# CAN.net
KiCad netlist of a schematic drawn in Altium Designer
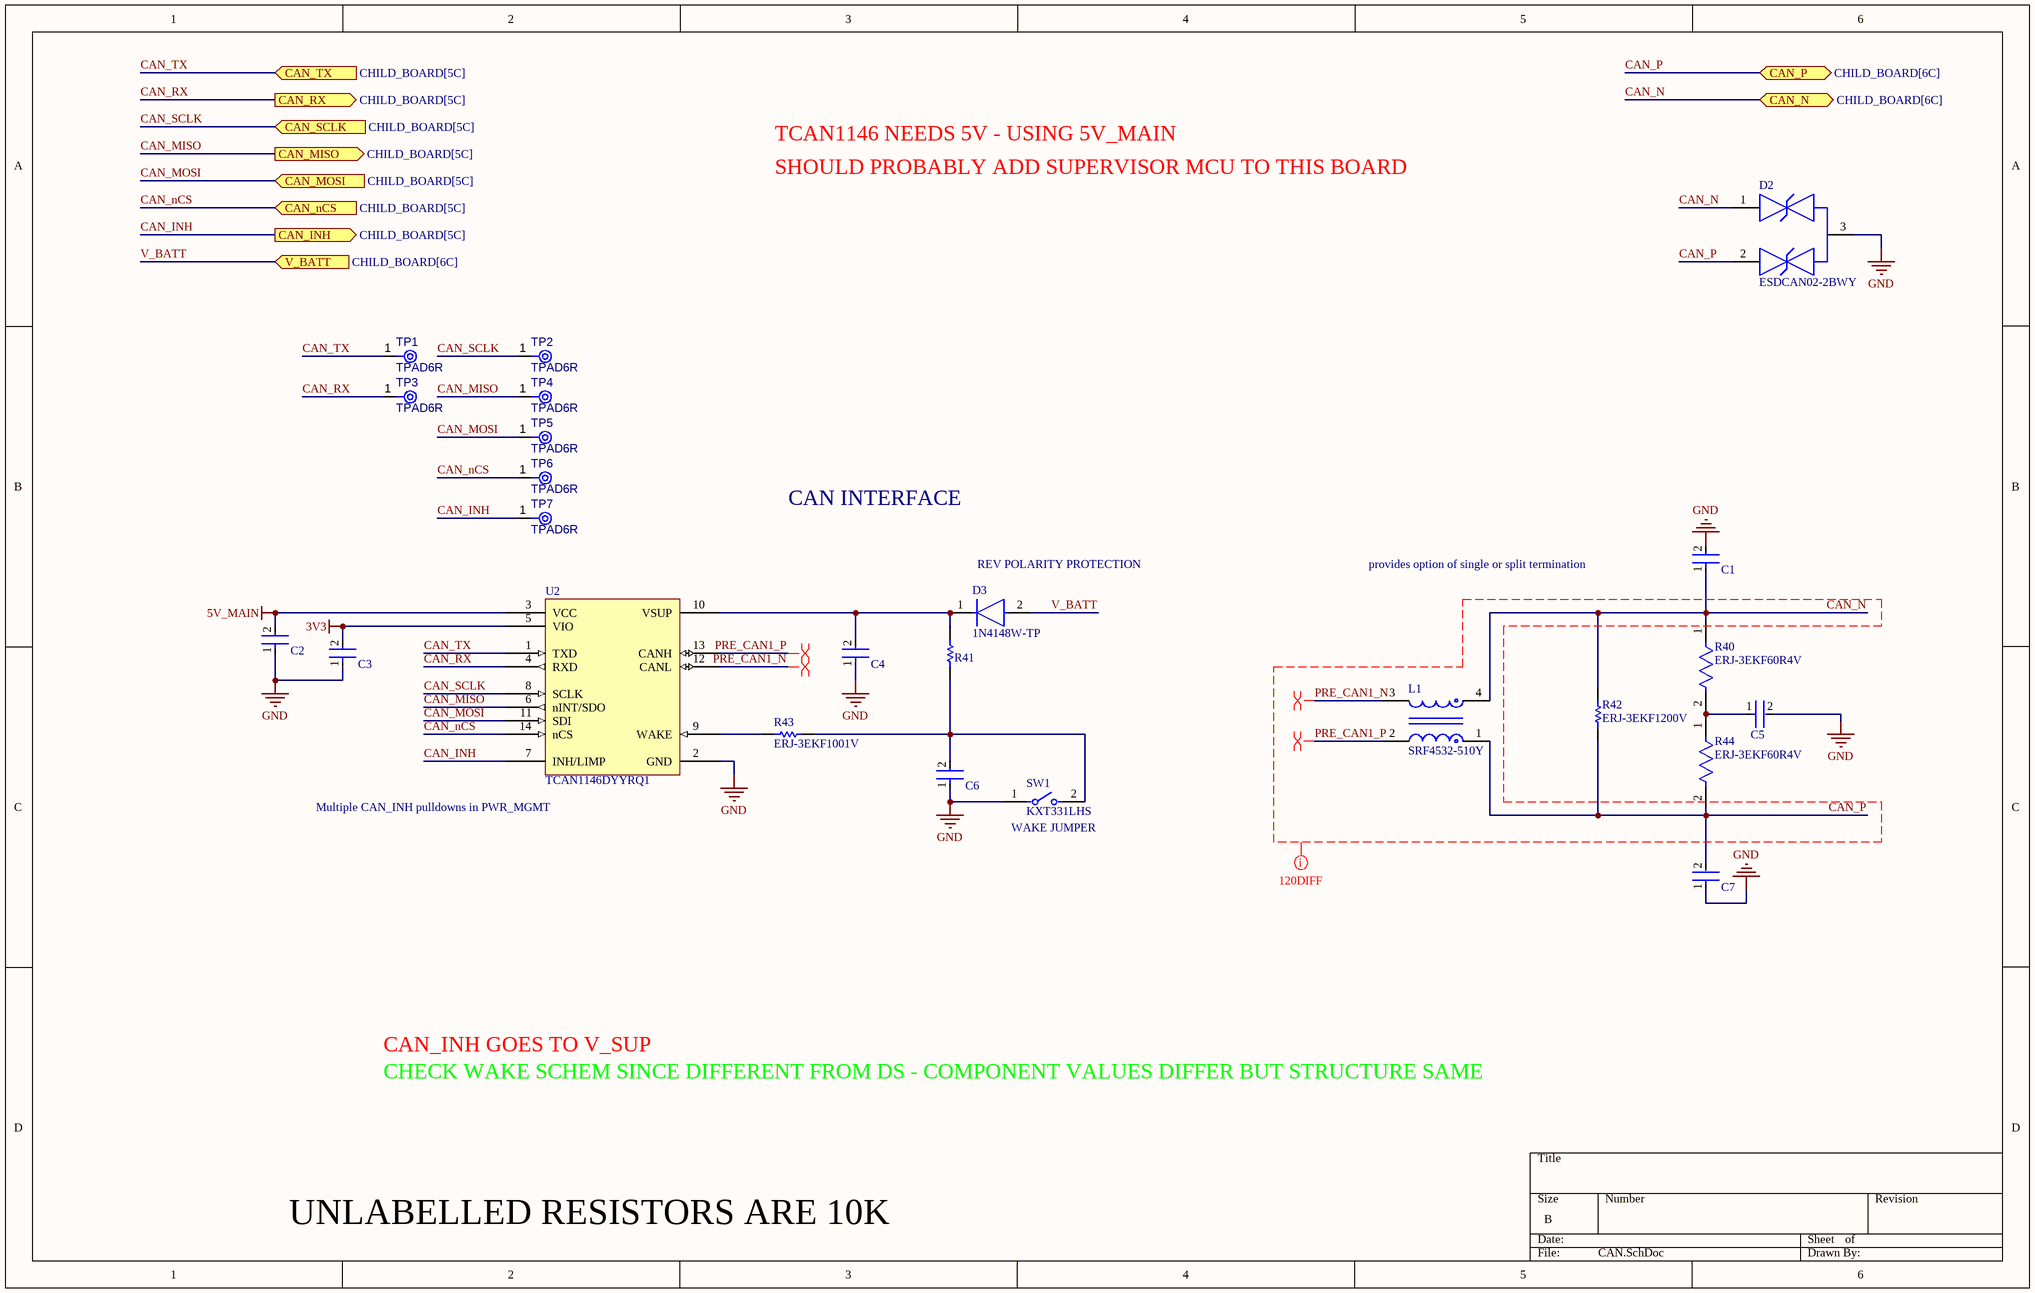
[diagram p0: CAN.SchDoc]

(export (version "E")
  (design (tool "Eeschema 10.0.6"))
  (components
    (comp (ref "C1")
      (value "C0402C104K8PACTU")
      (footprint "FP-C0402-BB-MFG")
      (description "CAP CER 0.1UF 10V X5R 0402")
      (fields (field (name "MANUFACTURER") "Kemet") (field (name "TOLERANCE") "0.1"))
      (libsource (lib "Altium Content Vault") (part "b4654b650e69147ec39a6b967a45e02"))
    )
    (comp (ref "C2")
      (value "C0402C104K8PACTU")
      (footprint "FP-C0402-BB-MFG")
      (description "CAP CER 0.1UF 10V X5R 0402")
      (fields (field (name "MANUFACTURER") "Kemet") (field (name "TOLERANCE") "0.1"))
      (libsource (lib "Altium Content Vault") (part "b4654b650e69147ec39a6b967a45e02"))
    )
    (comp (ref "C3")
      (value "C0402C104K8PACTU")
      (footprint "FP-C0402-BB-MFG")
      (description "CAP CER 0.1UF 10V X5R 0402")
      (fields (field (name "MANUFACTURER") "Kemet") (field (name "TOLERANCE") "0.1"))
      (libsource (lib "Altium Content Vault") (part "b4654b650e69147ec39a6b967a45e02"))
    )
    (comp (ref "C4")
      (value "C0402C104K8PACTU")
      (footprint "FP-C0402-BB-MFG")
      (description "CAP CER 0.1UF 10V X5R 0402")
      (fields (field (name "MANUFACTURER") "Kemet") (field (name "TOLERANCE") "0.1"))
      (libsource (lib "Altium Content Vault") (part "b4654b650e69147ec39a6b967a45e02"))
    )
    (comp (ref "C5")
      (value "C0402C104K8PACTU")
      (footprint "FP-C0402-BB-MFG")
      (description "CAP CER 0.1UF 10V X5R 0402")
      (fields (field (name "MANUFACTURER") "Kemet") (field (name "TOLERANCE") "0.1"))
      (libsource (lib "Altium Content Vault") (part "b4654b650e69147ec39a6b967a45e02"))
    )
    (comp (ref "C6")
      (value "C0402C104K8PACTU")
      (footprint "FP-C0402-BB-MFG")
      (description "CAP CER 0.1UF 10V X5R 0402")
      (fields (field (name "MANUFACTURER") "Kemet") (field (name "TOLERANCE") "0.1"))
      (libsource (lib "Altium Content Vault") (part "b4654b650e69147ec39a6b967a45e02"))
    )
    (comp (ref "C7")
      (value "C0402C104K8PACTU")
      (footprint "FP-C0402-BB-MFG")
      (description "CAP CER 0.1UF 10V X5R 0402")
      (fields (field (name "MANUFACTURER") "Kemet") (field (name "TOLERANCE") "0.1"))
      (libsource (lib "Altium Content Vault") (part "b4654b650e69147ec39a6b967a45e02"))
    )
    (comp (ref "D2")
      (value "ESDCAN02-2BWY")
      (footprint "FP-SOT323-3L-MFG")
      (description "TVS DIODE 26.5V 44V SOT323-3")
      (fields
        (field (name "MANUFACTURER") "STMicroelectronics")
        (field (name "OCTOPART") "https://octopart.com/esdcan02-2bwy-stmicroelectronics-58631133")
      )
      (libsource (lib "Altium Content Vault") (part "0b9019fb5e52ed66df21ec1535be59d"))
    )
    (comp (ref "D3")
      (value "1N4148W-TP")
      (footprint "FP-SOD-123-IPC_A")
      (description "DIODE GEN PURP 100V 150MA SOD123")
      (libsource (lib "Altium Content Vault") (part "d7152d700b627762746794eb795d46e"))
    )
    (comp (ref "L1")
      (value "SRF4532-510Y")
      (footprint "FP-SRF4532-MFG")
      (description "CMC 51UH 200MA 2LN 2KOHM SMD")
      (fields (field (name "TOLERANCE") "50%"))
      (libsource (lib "Altium Content Vault") (part "aca3f6a10b859f211cca95010157f3b"))
    )
    (comp (ref "R40")
      (value "ERJ-3EKF60R4V")
      (footprint "FP-ERJ3EK-IPC_C")
      (description "RES SMD 60.4 OHM 1% 1/10W 0603")
      (fields (field (name "TOLERANCE") "1%"))
      (libsource (lib "Altium Content Vault") (part "1029c3af85768c4190bb7ad29bc67b5"))
    )
    (comp (ref "R41")
      (value "ERJ3EKF1002V")
      (footprint "RESC1609X55X30LL15T15")
      (description "Chip Resistor, 10 KOhm, +/- 1%, 0.1 W, -55 to 155 degC, 0603 (1608 Metric), RoHS, Tape and Reel")
      (fields (field (name "TOLERANCE") "1%") (field (name "MANUFACTURER") "Panasonic"))
      (libsource (lib "Altium Content Vault") (part "RES-2"))
    )
    (comp (ref "R42")
      (value "ERJ-3EKF1200V")
      (footprint "RESC1609X55X30ML15T15")
      (description "Chip Resistor, 120 Ohm, +/- 1%, 0.1 W, -55 to 155 degC, 0603 (1608 Metric), RoHS, Tape and Reel")
      (fields (field (name "TOLERANCE") "1%") (field (name "MANUFACTURER") "Panasonic"))
      (libsource (lib "Altium Content Vault") (part "RES-2"))
    )
    (comp (ref "R43")
      (value "ERJ-3EKF1001V")
      (footprint "RESC1608X55X30LL15T15")
      (fields (field (name "MANUFACTURER") "Panasonic"))
      (libsource (lib "Altium Content Vault") (part "RES"))
    )
    (comp (ref "R44")
      (value "ERJ-3EKF60R4V")
      (footprint "FP-ERJ3EK-IPC_C")
      (description "RES SMD 60.4 OHM 1% 1/10W 0603")
      (fields (field (name "TOLERANCE") "1%"))
      (libsource (lib "Altium Content Vault") (part "1029c3af85768c4190bb7ad29bc67b5"))
    )
    (comp (ref "SW1")
      (value "KXT331LHS")
      (footprint "FP-KXT331LHS-MFG")
      (description "SWITCH TACTILE SPST-NO 0.02A 15V")
      (libsource (lib "Altium Content Vault") (part "bb27bde45df87f1f469753f287ef5ae"))
    )
    (comp (ref "TP1")
      (value "TPAD6R")
      (footprint "TP06R")
      (description "0.6mm round")
      (libsource (lib "uORocketry Hardware") (part "CMP-001-0001-4"))
    )
    (comp (ref "TP2")
      (value "TPAD6R")
      (footprint "TP06R")
      (description "0.6mm round")
      (libsource (lib "uORocketry Hardware") (part "CMP-001-0001-4"))
    )
    (comp (ref "TP3")
      (value "TPAD6R")
      (footprint "TP06R")
      (description "0.6mm round")
      (libsource (lib "uORocketry Hardware") (part "CMP-001-0001-4"))
    )
    (comp (ref "TP4")
      (value "TPAD6R")
      (footprint "TP06R")
      (description "0.6mm round")
      (libsource (lib "uORocketry Hardware") (part "CMP-001-0001-4"))
    )
    (comp (ref "TP5")
      (value "TPAD6R")
      (footprint "TP06R")
      (description "0.6mm round")
      (libsource (lib "uORocketry Hardware") (part "CMP-001-0001-4"))
    )
    (comp (ref "TP6")
      (value "TPAD6R")
      (footprint "TP06R")
      (description "0.6mm round")
      (libsource (lib "uORocketry Hardware") (part "CMP-001-0001-4"))
    )
    (comp (ref "TP7")
      (value "TPAD6R")
      (footprint "TP06R")
      (description "0.6mm round")
      (libsource (lib "uORocketry Hardware") (part "CMP-001-0001-4"))
    )
    (comp (ref "U2")
      (value "TCAN1146DYYRQ1")
      (footprint "TCAN1146DYYRQ1-Footprint-1")
      (libsource (lib "uORocketry Hardware") (part "TCAN1146DYYRQ1"))
    )
  )
  (nets
    (net (code "1") (name "/CAN_INH") (class "Default")
      (node (ref "TP7") (pin "1") (pinfunction "TP_1") (pintype "passive"))
      (node (ref "U2") (pin "7") (pinfunction "INH/LIMP_7") (pintype "passive"))
    )
    (net (code "2") (name "/CAN_MISO") (class "Default")
      (node (ref "TP4") (pin "1") (pinfunction "TP_1") (pintype "passive"))
      (node (ref "U2") (pin "6") (pinfunction "nINT/SDO_6") (pintype "output"))
    )
    (net (code "3") (name "/CAN_MOSI") (class "Default")
      (node (ref "TP5") (pin "1") (pinfunction "TP_1") (pintype "passive"))
      (node (ref "U2") (pin "11") (pinfunction "SDI_11") (pintype "input"))
    )
    (net (code "4") (name "/CAN_N") (class "Default")
      (node (ref "C1") (pin "1") (pinfunction "1_1") (pintype "passive"))
      (node (ref "D2") (pin "1") (pinfunction "1_1") (pintype "passive"))
      (node (ref "L1") (pin "4") (pinfunction "4_4") (pintype "passive"))
      (node (ref "R40") (pin "1") (pinfunction "1_1") (pintype "passive"))
      (node (ref "R42") (pin "1") (pinfunction "1_1") (pintype "passive"))
    )
    (net (code "5") (name "/CAN_P") (class "Default")
      (node (ref "C7") (pin "2") (pinfunction "2_2") (pintype "passive"))
      (node (ref "D2") (pin "2") (pinfunction "2_2") (pintype "passive"))
      (node (ref "L1") (pin "1") (pinfunction "1_1") (pintype "passive"))
      (node (ref "R42") (pin "2") (pinfunction "2_2") (pintype "passive"))
      (node (ref "R44") (pin "2") (pinfunction "2_2") (pintype "passive"))
    )
    (net (code "6") (name "/CAN_RX") (class "Default")
      (node (ref "TP3") (pin "1") (pinfunction "TP_1") (pintype "passive"))
      (node (ref "U2") (pin "4") (pinfunction "RXD_4") (pintype "output"))
    )
    (net (code "7") (name "/CAN_SCLK") (class "Default")
      (node (ref "TP2") (pin "1") (pinfunction "TP_1") (pintype "passive"))
      (node (ref "U2") (pin "8") (pinfunction "SCLK_8") (pintype "input"))
    )
    (net (code "8") (name "/CAN_TX") (class "Default")
      (node (ref "TP1") (pin "1") (pinfunction "TP_1") (pintype "passive"))
      (node (ref "U2") (pin "1") (pinfunction "TXD_1") (pintype "input"))
    )
    (net (code "9") (name "/CAN_nCS") (class "Default")
      (node (ref "TP6") (pin "1") (pinfunction "TP_1") (pintype "passive"))
      (node (ref "U2") (pin "14") (pinfunction "nCS_14") (pintype "input"))
    )
    (net (code "10") (name "/PRE_CAN1_N") (class "Default")
      (node (ref "L1") (pin "3") (pinfunction "3_3") (pintype "passive"))
      (node (ref "U2") (pin "12") (pinfunction "CANL_12") (pintype "bidirectional"))
    )
    (net (code "11") (name "/PRE_CAN1_P") (class "Default")
      (node (ref "L1") (pin "2") (pinfunction "2_2") (pintype "passive"))
      (node (ref "U2") (pin "13") (pinfunction "CANH_13") (pintype "bidirectional"))
    )
    (net (code "12") (name "/V_BATT") (class "Default")
      (node (ref "D3") (pin "2") (pinfunction "A_2") (pintype "passive"))
    )
    (net (code "13") (name "3V3") (class "Default")
      (node (ref "C3") (pin "2") (pinfunction "2_2") (pintype "passive"))
      (node (ref "U2") (pin "5") (pinfunction "VIO_5") (pintype "power_in"))
    )
    (net (code "14") (name "5V_MAIN") (class "Default")
      (node (ref "C2") (pin "2") (pinfunction "2_2") (pintype "passive"))
      (node (ref "U2") (pin "3") (pinfunction "VCC_3") (pintype "power_in"))
    )
    (net (code "15") (name "GND") (class "Default")
      (node (ref "C1") (pin "2") (pinfunction "2_2") (pintype "passive"))
      (node (ref "C2") (pin "1") (pinfunction "1_1") (pintype "passive"))
      (node (ref "C3") (pin "1") (pinfunction "1_1") (pintype "passive"))
      (node (ref "C4") (pin "1") (pinfunction "1_1") (pintype "passive"))
      (node (ref "C5") (pin "2") (pinfunction "2_2") (pintype "passive"))
      (node (ref "C6") (pin "1") (pinfunction "1_1") (pintype "passive"))
      (node (ref "C7") (pin "1") (pinfunction "1_1") (pintype "passive"))
      (node (ref "D2") (pin "3") (pinfunction "3_3") (pintype "passive"))
      (node (ref "SW1") (pin "1") (pinfunction "1_1") (pintype "passive"))
      (node (ref "U2") (pin "2") (pinfunction "GND_2") (pintype "power_in"))
    )
    (net (code "16") (name "Net-(C5-Pad1)") (class "Default")
      (node (ref "C5") (pin "1") (pinfunction "1_1") (pintype "passive"))
      (node (ref "R40") (pin "2") (pinfunction "2_2") (pintype "passive"))
      (node (ref "R44") (pin "1") (pinfunction "1_1") (pintype "passive"))
    )
    (net (code "17") (name "Net-(C6-Pad2)") (class "Default")
      (node (ref "C6") (pin "2") (pinfunction "2_2") (pintype "passive"))
      (node (ref "R41") (pin "2") (pinfunction "2_2") (pintype "passive"))
      (node (ref "R43") (pin "2") (pinfunction "2_2") (pintype "passive"))
      (node (ref "SW1") (pin "2") (pinfunction "2_2") (pintype "passive"))
    )
    (net (code "18") (name "Net-(D3-C)") (class "Default")
      (node (ref "C4") (pin "2") (pinfunction "2_2") (pintype "passive"))
      (node (ref "D3") (pin "1") (pinfunction "C_1") (pintype "passive"))
      (node (ref "R41") (pin "1") (pinfunction "1_1") (pintype "passive"))
      (node (ref "U2") (pin "10") (pinfunction "VSUP_10") (pintype "power_in"))
    )
    (net (code "19") (name "Net-(U2-WAKE)") (class "Default")
      (node (ref "R43") (pin "1") (pinfunction "1_1") (pintype "passive"))
      (node (ref "U2") (pin "9") (pinfunction "WAKE_9") (pintype "input"))
    )
  )
)
